# SARADC.net
KiCad netlist of a schematic drawn in Altium Designer
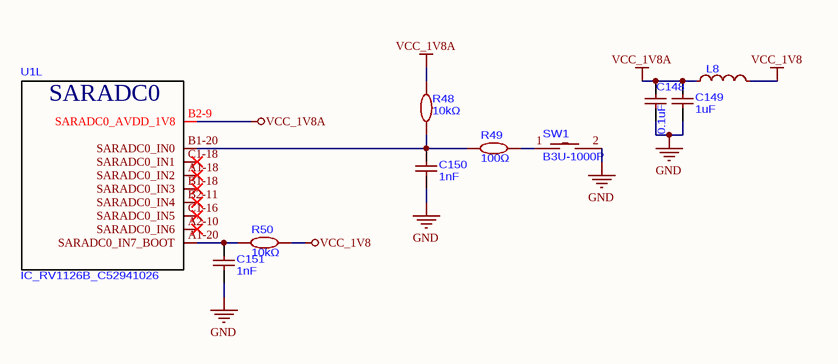
[diagram p0: SARADC.SchDoc]

(export (version "E")
  (design (tool "Eeschema 10.0.6"))
  (components
    (comp (ref "C148")
      (value "0.1uF")
      (footprint "C0201")
      (description "0.1uF ±10% 6.3V Ceramic Capacitor X5R 0201")
      (libsource (lib "Schlib1") (part "CAP_100nF-6.3V-10%-0201_1"))
    )
    (comp (ref "C149")
      (value "1uF")
      (footprint "C0201")
      (description "1uF ±10% 6.3V Ceramic Capacitor X5R 0201")
      (libsource (lib "Schlib1") (part "CAP_1uF-6.3V-10%-0201"))
    )
    (comp (ref "C150")
      (value "1nF")
      (footprint "C0201")
      (description "CAP CER 1nF 50V X7R 0201")
      (libsource (lib "Schlib1") (part "CAP_1nF-50V-10%-0201"))
    )
    (comp (ref "C151")
      (value "1nF")
      (footprint "C0201")
      (description "CAP CER 1nF 50V X7R 0201")
      (libsource (lib "Schlib1") (part "CAP_1nF-50V-10%-0201"))
    )
    (comp (ref "L8")
      (value "FERRITE BEAD 120Ω 0201 1LN")
      (footprint "R0201")
      (description "120 Ohms @ 100MHz 1 Power Line Ferrite Bead 0201 1A 130mOhm")
      (libsource (lib "Schlib1") (part "MPZ0603S121HT000"))
    )
    (comp (ref "R48")
      (value "10kΩ")
      (footprint "R0201")
      (description "RES 10KΩ ±1% 50mW 0201")
      (libsource (lib "Schlib1") (part "RES_10K-50mW-1%-0201"))
    )
    (comp (ref "R49")
      (value "100Ω")
      (footprint "R0201")
      (description "RES 100Ω ±1% 50mW 0201")
      (libsource (lib "Schlib1") (part "RES_100OHM-50mW-1%-0201"))
    )
    (comp (ref "R50")
      (value "10kΩ")
      (footprint "R0201")
      (description "RES 10KΩ ±1% 50mW 0201")
      (libsource (lib "Schlib1") (part "RES_10K-50mW-1%-0201"))
    )
    (comp (ref "SW1")
      (value "B3U-1000P")
      (footprint "KEY-SMD_B3U-1000PM")
      (description "12V 2.5mm Round Button 3mm SPST 50mA SMD,3x2.5mm Tactile Switches ROHS")
      (libsource (lib "Schlib1") (part "B3U-1000P"))
    )
    (comp (ref "U1")
      (value "IC_RV1126B_C52941026")
      (footprint "CCSP-491_L14.0-W14.0-TL_RV1126B")
      (libsource (lib "Schlib1") (part "IC_RV1126B_C52941026"))
    )
  )
  (nets
    (net (code "1") (name "GND") (class "Default")
      (node (ref "C148") (pin "1") (pinfunction "1_1") (pintype "passive"))
      (node (ref "C149") (pin "2") (pinfunction "2_2") (pintype "passive"))
      (node (ref "C150") (pin "1") (pinfunction "1_1") (pintype "passive"))
      (node (ref "C151") (pin "1") (pinfunction "1_1") (pintype "passive"))
      (node (ref "SW1") (pin "2") (pinfunction "2_2") (pintype "passive"))
    )
    (net (code "2") (name "Net-(R49-Pad2)") (class "Default")
      (node (ref "R49") (pin "2") (pinfunction "2_2") (pintype "passive"))
      (node (ref "SW1") (pin "1") (pinfunction "1_1") (pintype "passive"))
    )
    (net (code "3") (name "Net-(U1L-SARADC0_IN0)") (class "Default")
      (node (ref "C150") (pin "2") (pinfunction "2_2") (pintype "passive"))
      (node (ref "R48") (pin "1") (pinfunction "1_1") (pintype "passive"))
      (node (ref "R49") (pin "1") (pinfunction "1_1") (pintype "passive"))
      (node (ref "U1") (pin "B1-20") (pinfunction "SARADC0_IN0_B1-20") (pintype "passive"))
    )
    (net (code "4") (name "Net-(U1L-SARADC0_IN7_BOOT)") (class "Default")
      (node (ref "C151") (pin "2") (pinfunction "2_2") (pintype "passive"))
      (node (ref "R50") (pin "2") (pinfunction "2_2") (pintype "passive"))
      (node (ref "U1") (pin "A1-20") (pinfunction "SARADC0_IN7_BOOT_A1-20") (pintype "passive"))
    )
    (net (code "5") (name "VCC_1V8") (class "Default")
      (node (ref "L8") (pin "2") (pinfunction "2_2") (pintype "passive"))
      (node (ref "R50") (pin "1") (pinfunction "1_1") (pintype "passive"))
    )
    (net (code "6") (name "VCC_1V8A") (class "Default")
      (node (ref "C148") (pin "2") (pinfunction "2_2") (pintype "passive"))
      (node (ref "C149") (pin "1") (pinfunction "1_1") (pintype "passive"))
      (node (ref "L8") (pin "1") (pinfunction "1_1") (pintype "passive"))
      (node (ref "R48") (pin "2") (pinfunction "2_2") (pintype "passive"))
      (node (ref "U1") (pin "B2-9") (pinfunction "SARADC0_AVDD_1V8_B2-9") (pintype "passive"))
    )
    (net (code "7") (name "unconnected-(U1L-SARADC0_IN1-PadC1-18)") (class "Default")
      (node (ref "U1") (pin "C1-18") (pinfunction "SARADC0_IN1_C1-18") (pintype "passive+no_connect"))
    )
    (net (code "8") (name "unconnected-(U1L-SARADC0_IN2-PadA1-18)") (class "Default")
      (node (ref "U1") (pin "A1-18") (pinfunction "SARADC0_IN2_A1-18") (pintype "passive+no_connect"))
    )
    (net (code "9") (name "unconnected-(U1L-SARADC0_IN3-PadB1-18)") (class "Default")
      (node (ref "U1") (pin "B1-18") (pinfunction "SARADC0_IN3_B1-18") (pintype "passive+no_connect"))
    )
    (net (code "10") (name "unconnected-(U1L-SARADC0_IN4-PadB2-11)") (class "Default")
      (node (ref "U1") (pin "B2-11") (pinfunction "SARADC0_IN4_B2-11") (pintype "passive+no_connect"))
    )
    (net (code "11") (name "unconnected-(U1L-SARADC0_IN5-PadC1-16)") (class "Default")
      (node (ref "U1") (pin "C1-16") (pinfunction "SARADC0_IN5_C1-16") (pintype "passive+no_connect"))
    )
    (net (code "12") (name "unconnected-(U1L-SARADC0_IN6-PadA2-10)") (class "Default")
      (node (ref "U1") (pin "A2-10") (pinfunction "SARADC0_IN6_A2-10") (pintype "passive+no_connect"))
    )
  )
)
